# GPS_radiologger_v15.net
KiCad netlist of a schematic drawn in EAGLE
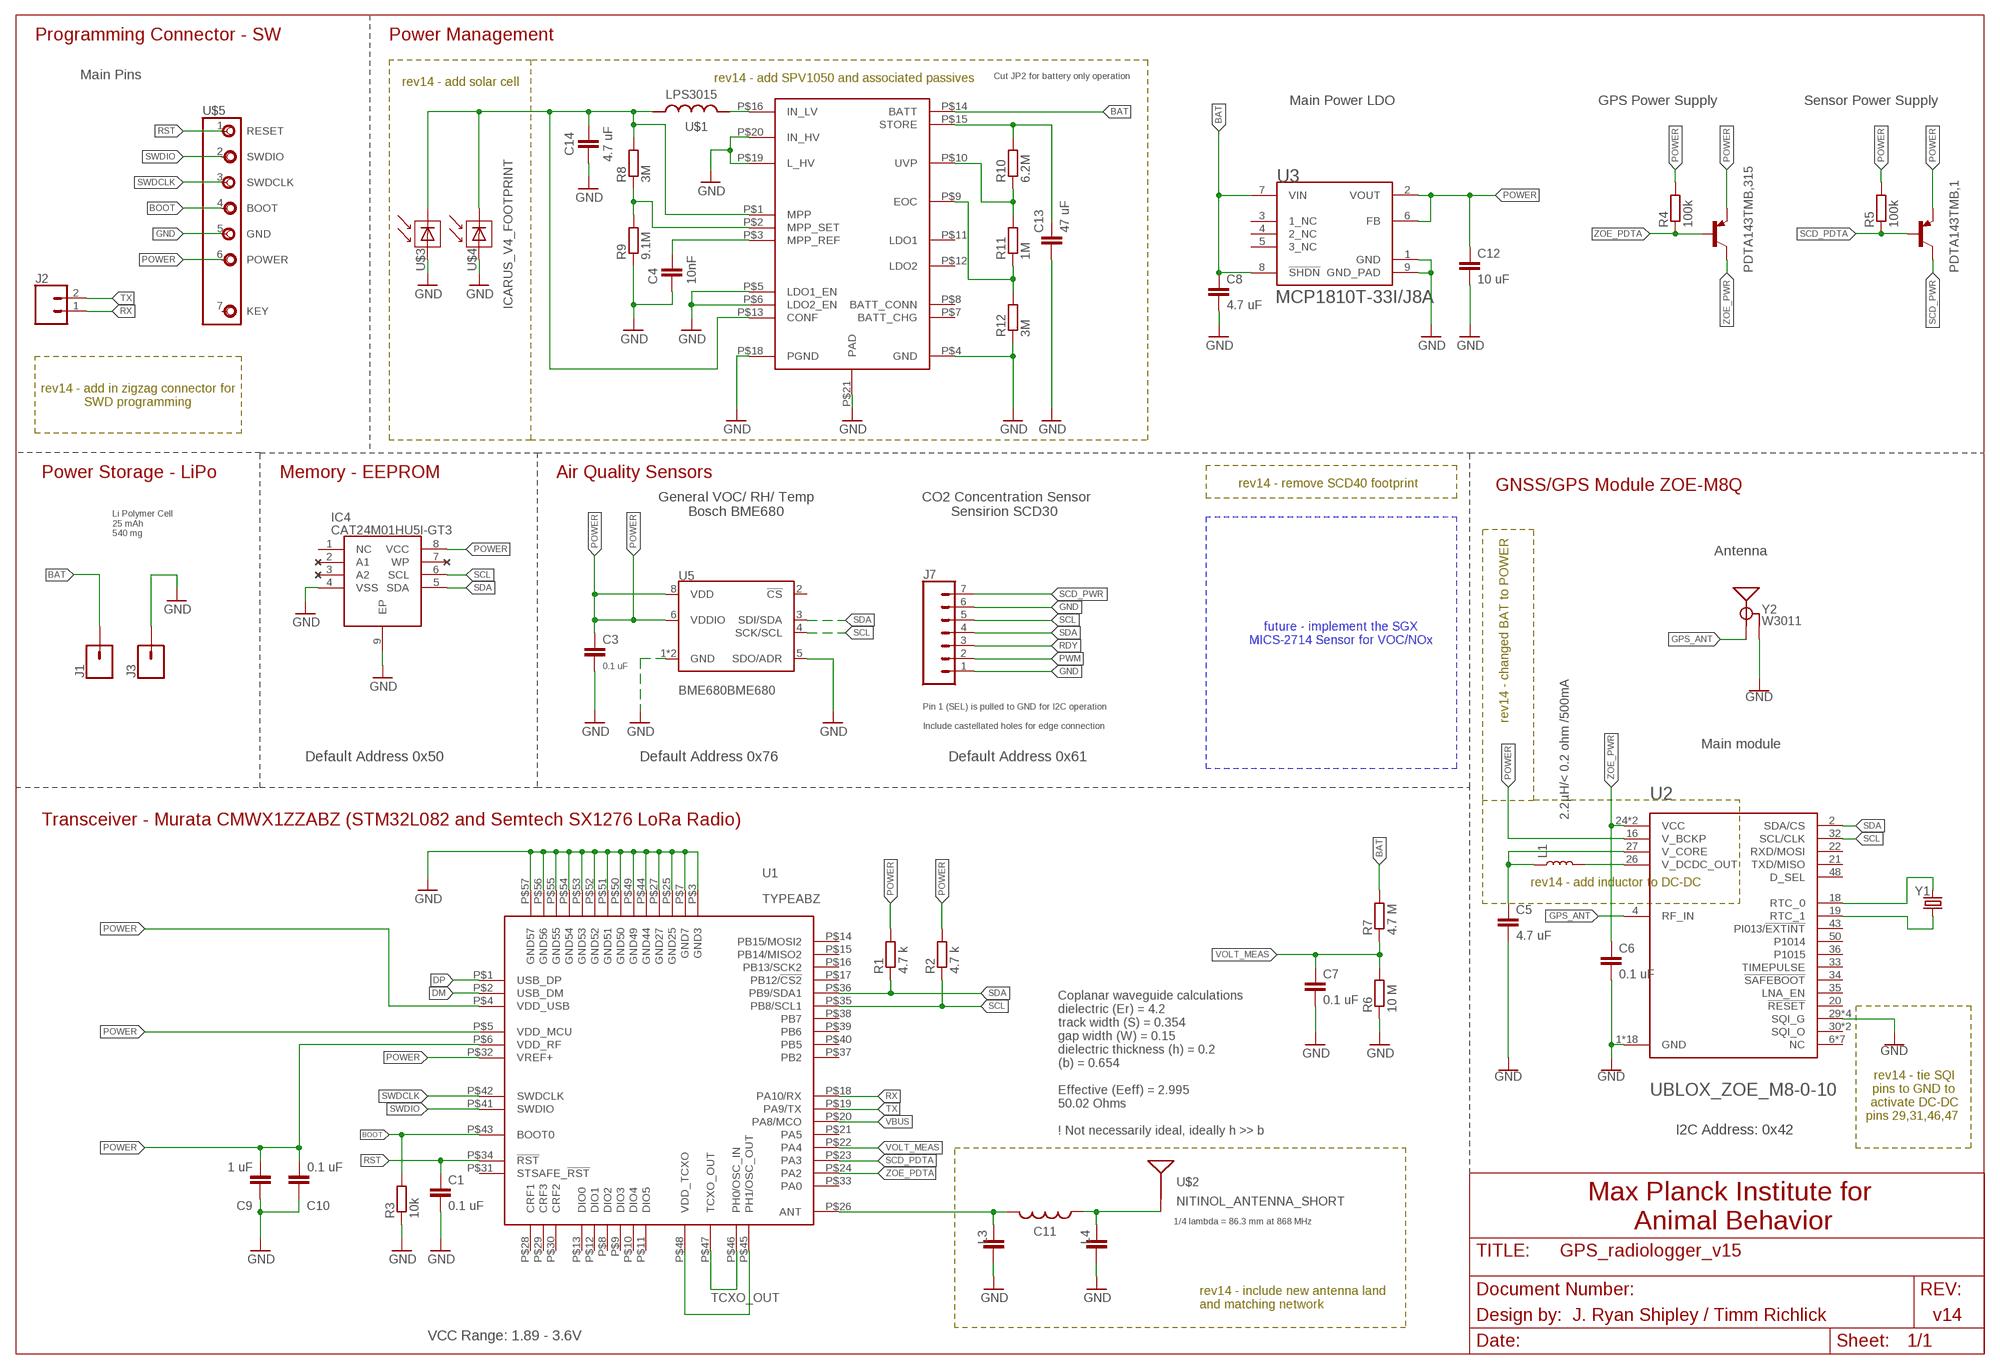
[diagram p0: schematic, sheet 1]

(export (version "E")
  (design (tool "Eeschema 10.0.6"))
  (components
    (comp (ref "C1")
      (value "0.1 uF")
      (footprint "eagle-import:C0201")
      (libsource (lib "eagle-import") (part "C-EUC0201"))
    )
    (comp (ref "C3")
      (value "0.1 uF")
      (footprint "eagle-import:C0201")
      (libsource (lib "eagle-import") (part "C-EUC0201"))
    )
    (comp (ref "C4")
      (value "10nF")
      (footprint "eagle-import:C0201")
      (libsource (lib "eagle-import") (part "C-EUC0201"))
    )
    (comp (ref "C5")
      (value "4.7 uF")
      (footprint "eagle-import:C0201")
      (libsource (lib "eagle-import") (part "C-EUC0201"))
    )
    (comp (ref "C6")
      (value "0.1 uF")
      (footprint "eagle-import:C0201")
      (libsource (lib "eagle-import") (part "C-EUC0201"))
    )
    (comp (ref "C7")
      (value "0.1 uF")
      (footprint "eagle-import:C0201")
      (libsource (lib "eagle-import") (part "C-EUC0201"))
    )
    (comp (ref "C8")
      (value "4.7 uF")
      (footprint "eagle-import:C0201")
      (libsource (lib "eagle-import") (part "C-EUC0201"))
    )
    (comp (ref "C9")
      (value "1 uF")
      (footprint "eagle-import:C0201")
      (libsource (lib "eagle-import") (part "C-EUC0201"))
    )
    (comp (ref "C10")
      (value "0.1 uF")
      (footprint "eagle-import:C0201")
      (libsource (lib "eagle-import") (part "C-EUC0201"))
    )
    (comp (ref "C11")
      (value "0.1uF")
      (footprint "eagle-import:L0201")
      (libsource (lib "eagle-import") (part "L-USL0201"))
    )
    (comp (ref "C12")
      (value "10 uF")
      (footprint "eagle-import:C0201")
      (libsource (lib "eagle-import") (part "C-EUC0201"))
    )
    (comp (ref "C13")
      (value "47 uF")
      (footprint "eagle-import:C0805K")
      (libsource (lib "eagle-import") (part "C-EUC0805K"))
    )
    (comp (ref "C14")
      (value "4.7 uF")
      (footprint "eagle-import:C0201")
      (libsource (lib "eagle-import") (part "C-EUC0201"))
    )
    (comp (ref "IC4")
      (value "CAT24M01HU5I-GT3")
      (footprint "eagle-import:SON50P300X200X55-9N")
      (fields
        (field (name "MOUSER_PART_NUMBER") "863-CAT24M01HU5I-GT3")
        (field (name "RS_PART_NUMBER") "7814831P")
      )
      (libsource (lib "eagle-import") (part "CAT24M01HU5I-GT3"))
    )
    (comp (ref "J1")
      (value "CONN_01PTH_NO_SILK_YES_STOP")
      (footprint "eagle-import:1X01_NO_SILK")
      (libsource (lib "eagle-import") (part "CONN_01PTH_NO_SILK_YES_STOP"))
    )
    (comp (ref "J2")
      (value "CONN_021X02_NO_SILK")
      (footprint "eagle-import:1X02_NO_SILK")
      (libsource (lib "eagle-import") (part "CONN_021X02_NO_SILK"))
    )
    (comp (ref "J3")
      (value "CONN_01PTH_NO_SILK_YES_STOP")
      (footprint "eagle-import:1X01_NO_SILK")
      (libsource (lib "eagle-import") (part "CONN_01PTH_NO_SILK_YES_STOP"))
    )
    (comp (ref "J7")
      (value "CONN_07NO_SILK")
      (footprint "eagle-import:1X07_NO_SILK")
      (libsource (lib "eagle-import") (part "CONN_07NO_SILK"))
    )
    (comp (ref "L1")
      (value "2.2µH/< 0.2 ohm /500mA")
      (footprint "eagle-import:0805")
      (libsource (lib "eagle-import") (part "INDUCTOR-0805-3.3UH"))
    )
    (comp (ref "L3")
      (value "C-EUC0201")
      (footprint "eagle-import:C0201")
      (libsource (lib "eagle-import") (part "C-EUC0201"))
    )
    (comp (ref "L4")
      (value "C-EUC0201")
      (footprint "eagle-import:C0201")
      (libsource (lib "eagle-import") (part "C-EUC0201"))
    )
    (comp (ref "PDTA143TMB,1")
      (value "TINYPICO-PNPAMB")
      (footprint "eagle-import:SOT883(B)")
      (libsource (lib "eagle-import") (part "TINYPICO-PNPMBA"))
    )
    (comp (ref "PDTA143TMB,315")
      (value "TINYPICO-PNPAMB")
      (footprint "eagle-import:SOT883(B)")
      (libsource (lib "eagle-import") (part "TINYPICO-PNPMBA"))
    )
    (comp (ref "R1")
      (value "4.7 k")
      (footprint "eagle-import:R0201")
      (libsource (lib "eagle-import") (part "R-EU_R0201"))
    )
    (comp (ref "R2")
      (value "4.7 k")
      (footprint "eagle-import:R0201")
      (libsource (lib "eagle-import") (part "R-EU_R0201"))
    )
    (comp (ref "R3")
      (value "10k")
      (footprint "eagle-import:R0201")
      (libsource (lib "eagle-import") (part "R-EU_R0201"))
    )
    (comp (ref "R4")
      (value "100k")
      (footprint "eagle-import:R0201")
      (libsource (lib "eagle-import") (part "R-EU_R0201"))
    )
    (comp (ref "R5")
      (value "100k")
      (footprint "eagle-import:R0201")
      (libsource (lib "eagle-import") (part "R-EU_R0201"))
    )
    (comp (ref "R6")
      (value "10 M")
      (footprint "eagle-import:R0201")
      (libsource (lib "eagle-import") (part "R-EU_R0201"))
    )
    (comp (ref "R7")
      (value "4.7 M")
      (footprint "eagle-import:R0201")
      (libsource (lib "eagle-import") (part "R-EU_R0201"))
    )
    (comp (ref "R8")
      (value "3M")
      (footprint "eagle-import:R0201")
      (libsource (lib "eagle-import") (part "R-EU_R0201"))
    )
    (comp (ref "R9")
      (value "9.1M")
      (footprint "eagle-import:R0201")
      (libsource (lib "eagle-import") (part "R-EU_R0201"))
    )
    (comp (ref "R10")
      (value "6.2M")
      (footprint "eagle-import:R0201")
      (libsource (lib "eagle-import") (part "R-EU_R0201"))
    )
    (comp (ref "R11")
      (value "1M")
      (footprint "eagle-import:R0201")
      (libsource (lib "eagle-import") (part "R-EU_R0201"))
    )
    (comp (ref "R12")
      (value "3M")
      (footprint "eagle-import:R0201")
      (libsource (lib "eagle-import") (part "R-EU_R0201"))
    )
    (comp (ref "U$1")
      (value "LPS3015")
      (footprint "eagle-import:LPS_3015")
      (libsource (lib "eagle-import") (part "LPS3015"))
    )
    (comp (ref "U$2")
      (value "NITINOL_ANTENNA_SHORT")
      (footprint "eagle-import:ICARUS_NITINOL_ANTENNA_SHORT")
      (libsource (lib "eagle-import") (part "NITINOL_ANTENNA_SHORT"))
    )
    (comp (ref "U$3")
      (value "ICARUS_V4_FOOTPRINT")
      (footprint "eagle-import:ICARUS_FULL_FOOTPRINT")
      (libsource (lib "eagle-import") (part "ICARUS_V4_FOOTPRINT"))
    )
    (comp (ref "U$4")
      (value "ICARUS_V4_FOOTPRINT")
      (footprint "eagle-import:ICARUS_FULL_FOOTPRINT")
      (libsource (lib "eagle-import") (part "ICARUS_V4_FOOTPRINT"))
    )
    (comp (ref "U$5")
      (value "ALBERT_ZIGZAG-ISP")
      (footprint "eagle-import:ALBERT_ZIGZAG-ISP")
      (libsource (lib "eagle-import") (part "ALBERT_ZIGZAG-ISP"))
    )
    (comp (ref "U1")
      (value "TYPEABZ")
      (footprint "eagle-import:TYPEABZ")
      (libsource (lib "eagle-import") (part "TYPEABZ"))
    )
    (comp (ref "U2")
      (value "UBLOX_ZOE_M8-0-10")
      (footprint "eagle-import:UBLOX_ZOE_M8-0-10")
      (libsource (lib "eagle-import") (part "UBLOX_ZOE_M8-0-10"))
    )
    (comp (ref "U3")
      (value "MICROCHIP_MCP1810T-33I-J8AMICROCHIP_MCP1810T-33I-J8A_0_0")
      (footprint "eagle-import:MICROCHIP_MCP1810T-33I-J8A_0")
      (fields
        (field (name "DIGIKEY_PART_NUMBER") "MCP1810T-33I/J8ACT-ND")
        (field (name "MF") "Microchip")
        (field (name "MOUSER_PART_NUMBER") "579-MCP1810T-33I/J8A")
      )
      (libsource (lib "eagle-import") (part "MICROCHIP_MCP1810T-33I-J8AMICROCHIP_MCP1810T-33I-J8A_0_0"))
    )
    (comp (ref "U4")
      (value "SPV1050")
      (footprint "eagle-import:SPV1050")
      (libsource (lib "eagle-import") (part "SPV1050"))
    )
    (comp (ref "U5")
      (value "BME680BME680")
      (footprint "eagle-import:LGA3.0X3.0")
      (libsource (lib "eagle-import") (part "BME680BME680"))
    )
    (comp (ref "Y1")
      (value "32.768kHz")
      (footprint "eagle-import:CRYSTAL-SMD-1.0X1.2MM")
      (libsource (lib "eagle-import") (part "CRYSTAL-32.768KHZ"))
    )
    (comp (ref "Y2")
      (value "W3011")
      (footprint "eagle-import:W3011")
      (libsource (lib "eagle-import") (part "GPS_CHIP_ANTENNAW3011"))
    )
  )
  (nets
    (net (code "1") (name "/TCXO_OUT") (class "Default")
      (node (ref "U1") (pin "P$46") (pinfunction "PH0/OSC_IN_P$46") (pintype "bidirectional"))
      (node (ref "U1") (pin "P$47") (pinfunction "TCXO_OUT_P$47") (pintype "bidirectional"))
    )
    (net (code "2") (name "BAT") (class "Default")
      (node (ref "C8") (pin "1") (pinfunction "1_1") (pintype "passive"))
      (node (ref "J1") (pin "1") (pinfunction "1_1") (pintype "passive"))
      (node (ref "R7") (pin "2") (pinfunction "2_2") (pintype "passive"))
      (node (ref "U3") (pin "7") (pinfunction "VIN_7") (pintype "bidirectional"))
      (node (ref "U3") (pin "8") (pinfunction "~{SHDN}_8") (pintype "bidirectional"))
      (node (ref "U4") (pin "P$14") (pinfunction "BATT_P$14") (pintype "bidirectional"))
    )
    (net (code "3") (name "BOOT") (class "Default")
      (node (ref "R3") (pin "2") (pinfunction "2_2") (pintype "passive"))
      (node (ref "U$5") (pin "4") (pinfunction "BOOT_4") (pintype "passive"))
      (node (ref "U1") (pin "P$43") (pinfunction "BOOT0_P$43") (pintype "bidirectional"))
    )
    (net (code "4") (name "DM") (class "Default")
      (node (ref "U1") (pin "P$2") (pinfunction "USB_DM_P$2") (pintype "bidirectional"))
    )
    (net (code "5") (name "DP") (class "Default")
      (node (ref "U1") (pin "P$1") (pinfunction "USB_DP_P$1") (pintype "bidirectional"))
    )
    (net (code "6") (name "GND") (class "Default")
      (node (ref "C1") (pin "2") (pinfunction "2_2") (pintype "passive"))
      (node (ref "C10") (pin "1") (pinfunction "1_1") (pintype "passive"))
      (node (ref "C12") (pin "2") (pinfunction "2_2") (pintype "passive"))
      (node (ref "C13") (pin "2") (pinfunction "2_2") (pintype "passive"))
      (node (ref "C14") (pin "2") (pinfunction "2_2") (pintype "passive"))
      (node (ref "C3") (pin "2") (pinfunction "2_2") (pintype "passive"))
      (node (ref "C4") (pin "2") (pinfunction "2_2") (pintype "passive"))
      (node (ref "C5") (pin "2") (pinfunction "2_2") (pintype "passive"))
      (node (ref "C6") (pin "2") (pinfunction "2_2") (pintype "passive"))
      (node (ref "C7") (pin "2") (pinfunction "2_2") (pintype "passive"))
      (node (ref "C8") (pin "2") (pinfunction "2_2") (pintype "passive"))
      (node (ref "C9") (pin "1") (pinfunction "1_1") (pintype "passive"))
      (node (ref "IC4") (pin "4") (pinfunction "VSS_4") (pintype "power_in"))
      (node (ref "IC4") (pin "9") (pinfunction "EP_9") (pintype "bidirectional"))
      (node (ref "J3") (pin "1") (pinfunction "1_1") (pintype "passive"))
      (node (ref "J7") (pin "1") (pinfunction "1_1") (pintype "passive"))
      (node (ref "J7") (pin "6") (pinfunction "6_6") (pintype "passive"))
      (node (ref "L3") (pin "2") (pinfunction "2_2") (pintype "passive"))
      (node (ref "L4") (pin "2") (pinfunction "2_2") (pintype "passive"))
      (node (ref "R12") (pin "1") (pinfunction "1_1") (pintype "passive"))
      (node (ref "R3") (pin "1") (pinfunction "1_1") (pintype "passive"))
      (node (ref "R6") (pin "1") (pinfunction "1_1") (pintype "passive"))
      (node (ref "R9") (pin "1") (pinfunction "1_1") (pintype "passive"))
      (node (ref "U$3") (pin "P$3") (pinfunction "MINUS_P$3") (pintype "passive"))
      (node (ref "U$4") (pin "P$3") (pinfunction "MINUS_P$3") (pintype "passive"))
      (node (ref "U$5") (pin "5") (pinfunction "GND_5") (pintype "passive"))
      (node (ref "U1") (pin "P$25") (pinfunction "GND25_P$25") (pintype "power_in"))
      (node (ref "U1") (pin "P$27") (pinfunction "GND27_P$27") (pintype "power_in"))
      (node (ref "U1") (pin "P$3") (pinfunction "GND3_P$3") (pintype "power_in"))
      (node (ref "U1") (pin "P$44") (pinfunction "GND44_P$44") (pintype "power_in"))
      (node (ref "U1") (pin "P$49") (pinfunction "GND49_P$49") (pintype "power_in"))
      (node (ref "U1") (pin "P$50") (pinfunction "GND50_P$50") (pintype "power_in"))
      (node (ref "U1") (pin "P$51") (pinfunction "GND51_P$51") (pintype "power_in"))
      (node (ref "U1") (pin "P$52") (pinfunction "GND52_P$52") (pintype "power_in"))
      (node (ref "U1") (pin "P$53") (pinfunction "GND53_P$53") (pintype "power_in"))
      (node (ref "U1") (pin "P$54") (pinfunction "GND54_P$54") (pintype "power_in"))
      (node (ref "U1") (pin "P$55") (pinfunction "GND55_P$55") (pintype "power_in"))
      (node (ref "U1") (pin "P$56") (pinfunction "GND56_P$56") (pintype "power_in"))
      (node (ref "U1") (pin "P$57") (pinfunction "GND57_P$57") (pintype "power_in"))
      (node (ref "U1") (pin "P$7") (pinfunction "GND7_P$7") (pintype "power_in"))
      (node (ref "U2") (pin "1") (pinfunction "GND_1") (pintype "power_in"))
      (node (ref "U2") (pin "10") (pinfunction "GND_10") (pintype "power_in"))
      (node (ref "U2") (pin "11") (pinfunction "GND_11") (pintype "power_in"))
      (node (ref "U2") (pin "12") (pinfunction "GND_12") (pintype "power_in"))
      (node (ref "U2") (pin "17") (pinfunction "GND_17") (pintype "power_in"))
      (node (ref "U2") (pin "23") (pinfunction "GND_23") (pintype "power_in"))
      (node (ref "U2") (pin "29") (pinfunction "SQI_G_29") (pintype "bidirectional"))
      (node (ref "U2") (pin "3") (pinfunction "GND_3") (pintype "power_in"))
      (node (ref "U2") (pin "31") (pinfunction "SQI_G_31") (pintype "bidirectional"))
      (node (ref "U2") (pin "37") (pinfunction "GND_37") (pintype "power_in"))
      (node (ref "U2") (pin "38") (pinfunction "GND_38") (pintype "power_in"))
      (node (ref "U2") (pin "39") (pinfunction "GND_39") (pintype "power_in"))
      (node (ref "U2") (pin "40") (pinfunction "GND_40") (pintype "power_in"))
      (node (ref "U2") (pin "41") (pinfunction "GND_41") (pintype "power_in"))
      (node (ref "U2") (pin "44") (pinfunction "GND_44") (pintype "power_in"))
      (node (ref "U2") (pin "46") (pinfunction "SQI_G_46") (pintype "bidirectional"))
      (node (ref "U2") (pin "47") (pinfunction "SQI_G_47") (pintype "bidirectional"))
      (node (ref "U2") (pin "49") (pinfunction "GND_49") (pintype "power_in"))
      (node (ref "U2") (pin "5") (pinfunction "GND_5") (pintype "power_in"))
      (node (ref "U2") (pin "7") (pinfunction "GND_7") (pintype "power_in"))
      (node (ref "U2") (pin "8") (pinfunction "GND_8") (pintype "power_in"))
      (node (ref "U2") (pin "9") (pinfunction "GND_9") (pintype "power_in"))
      (node (ref "U3") (pin "1") (pinfunction "GND_1") (pintype "bidirectional"))
      (node (ref "U3") (pin "9") (pinfunction "GND_PAD_9") (pintype "bidirectional"))
      (node (ref "U4") (pin "P$18") (pinfunction "PGND_P$18") (pintype "power_in"))
      (node (ref "U4") (pin "P$19") (pinfunction "L_HV_P$19") (pintype "power_in"))
      (node (ref "U4") (pin "P$20") (pinfunction "IN_HV_P$20") (pintype "power_in"))
      (node (ref "U4") (pin "P$21") (pinfunction "PAD_P$21") (pintype "power_in"))
      (node (ref "U4") (pin "P$4") (pinfunction "GND_P$4") (pintype "power_in"))
      (node (ref "U4") (pin "P$5") (pinfunction "LDO1_EN_P$5") (pintype "input"))
      (node (ref "U4") (pin "P$6") (pinfunction "LDO2_EN_P$6") (pintype "input"))
      (node (ref "U5") (pin "1") (pinfunction "GND_1") (pintype "bidirectional"))
      (node (ref "U5") (pin "5") (pinfunction "SDO/ADR_5") (pintype "bidirectional"))
      (node (ref "U5") (pin "7") (pinfunction "GND_7") (pintype "bidirectional"))
      (node (ref "Y2") (pin "2") (pinfunction "GND_2") (pintype "bidirectional"))
      (node (ref "Y2") (pin "3") (pinfunction "GND_3") (pintype "bidirectional"))
    )
    (net (code "7") (name "GPS_ANT") (class "Default")
      (node (ref "U2") (pin "4") (pinfunction "RF_IN_4") (pintype "bidirectional"))
      (node (ref "Y2") (pin "1") (pinfunction "SIGNAL_1") (pintype "bidirectional"))
    )
    (net (code "8") (name "Net-(C11-Pad1)") (class "Default")
      (node (ref "C11") (pin "1") (pinfunction "1_1") (pintype "passive"))
      (node (ref "L4") (pin "1") (pinfunction "1_1") (pintype "passive"))
      (node (ref "U$2") (pin "1") (pinfunction "SIGNAL_1") (pintype "bidirectional"))
      (node (ref "U$2") (pin "2") (pinfunction "SIGNAL_2") (pintype "bidirectional"))
      (node (ref "U$2") (pin "3") (pinfunction "SIGNAL_3") (pintype "bidirectional"))
    )
    (net (code "9") (name "Net-(U$1-1)") (class "Default")
      (node (ref "C14") (pin "1") (pinfunction "1_1") (pintype "passive"))
      (node (ref "R8") (pin "2") (pinfunction "2_2") (pintype "passive"))
      (node (ref "U$1") (pin "P$1") (pinfunction "1_P$1") (pintype "passive"))
      (node (ref "U$3") (pin "P$1") (pinfunction "PLUS_P$1") (pintype "passive"))
      (node (ref "U$4") (pin "P$1") (pinfunction "PLUS_P$1") (pintype "passive"))
      (node (ref "U4") (pin "P$1") (pinfunction "MPP_P$1") (pintype "input"))
      (node (ref "U4") (pin "P$13") (pinfunction "CONF_P$13") (pintype "input"))
    )
    (net (code "10") (name "Net-(U$1-2)") (class "Default")
      (node (ref "U$1") (pin "P$2") (pinfunction "2_P$2") (pintype "passive"))
      (node (ref "U4") (pin "P$16") (pinfunction "IN_LV_P$16") (pintype "power_in"))
    )
    (net (code "11") (name "Net-(U1-ANT)") (class "Default")
      (node (ref "C11") (pin "2") (pinfunction "2_2") (pintype "passive"))
      (node (ref "L3") (pin "1") (pinfunction "1_1") (pintype "passive"))
      (node (ref "U1") (pin "P$26") (pinfunction "ANT_P$26") (pintype "bidirectional"))
    )
    (net (code "12") (name "Net-(U1-PH1{slash}OSC_OUT)") (class "Default")
      (node (ref "U1") (pin "P$45") (pinfunction "PH1/OSC_OUT_P$45") (pintype "bidirectional"))
      (node (ref "U1") (pin "P$48") (pinfunction "VDD_TCXO_P$48") (pintype "power_in"))
    )
    (net (code "13") (name "Net-(U2-RTC_0)") (class "Default")
      (node (ref "U2") (pin "18") (pinfunction "RTC_0_18") (pintype "bidirectional"))
      (node (ref "Y1") (pin "P$2") (pinfunction "2_P$2") (pintype "passive"))
    )
    (net (code "14") (name "Net-(U2-RTC_1)") (class "Default")
      (node (ref "U2") (pin "19") (pinfunction "RTC_1_19") (pintype "bidirectional"))
      (node (ref "Y1") (pin "P$1") (pinfunction "1_P$1") (pintype "passive"))
    )
    (net (code "15") (name "Net-(U2-V_CORE)") (class "Default")
      (node (ref "C5") (pin "1") (pinfunction "1_1") (pintype "passive"))
      (node (ref "L1") (pin "1") (pinfunction "1_1") (pintype "passive"))
      (node (ref "U2") (pin "27") (pinfunction "V_CORE_27") (pintype "power_in"))
    )
    (net (code "16") (name "Net-(U2-V_DCDC_OUT)") (class "Default")
      (node (ref "L1") (pin "2") (pinfunction "2_2") (pintype "passive"))
      (node (ref "U2") (pin "26") (pinfunction "V_DCDC_OUT_26") (pintype "power_in"))
    )
    (net (code "17") (name "Net-(U4-EOC)") (class "Default")
      (node (ref "R11") (pin "1") (pinfunction "1_1") (pintype "passive"))
      (node (ref "R12") (pin "2") (pinfunction "2_2") (pintype "passive"))
      (node (ref "U4") (pin "P$9") (pinfunction "EOC_P$9") (pintype "input"))
    )
    (net (code "18") (name "Net-(U4-MPP_REF)") (class "Default")
      (node (ref "C4") (pin "1") (pinfunction "1_1") (pintype "passive"))
      (node (ref "U4") (pin "P$3") (pinfunction "MPP_REF_P$3") (pintype "input"))
    )
    (net (code "19") (name "Net-(U4-MPP_SET)") (class "Default")
      (node (ref "R8") (pin "1") (pinfunction "1_1") (pintype "passive"))
      (node (ref "R9") (pin "2") (pinfunction "2_2") (pintype "passive"))
      (node (ref "U4") (pin "P$2") (pinfunction "MPP_SET_P$2") (pintype "input"))
    )
    (net (code "20") (name "Net-(U4-STORE)") (class "Default")
      (node (ref "C13") (pin "1") (pinfunction "1_1") (pintype "passive"))
      (node (ref "R10") (pin "2") (pinfunction "2_2") (pintype "passive"))
      (node (ref "U4") (pin "P$15") (pinfunction "STORE_P$15") (pintype "bidirectional"))
    )
    (net (code "21") (name "Net-(U4-UVP)") (class "Default")
      (node (ref "R10") (pin "1") (pinfunction "1_1") (pintype "passive"))
      (node (ref "R11") (pin "2") (pinfunction "2_2") (pintype "passive"))
      (node (ref "U4") (pin "P$10") (pinfunction "UVP_P$10") (pintype "input"))
    )
    (net (code "22") (name "POWER") (class "Default")
      (node (ref "C10") (pin "2") (pinfunction "2_2") (pintype "passive"))
      (node (ref "C12") (pin "1") (pinfunction "1_1") (pintype "passive"))
      (node (ref "C3") (pin "1") (pinfunction "1_1") (pintype "passive"))
      (node (ref "C9") (pin "2") (pinfunction "2_2") (pintype "passive"))
      (node (ref "IC4") (pin "8") (pinfunction "VCC_8") (pintype "power_in"))
      (node (ref "PDTA143TMB,1") (pin "2") (pinfunction "E_2") (pintype "passive"))
      (node (ref "PDTA143TMB,315") (pin "2") (pinfunction "E_2") (pintype "passive"))
      (node (ref "R1") (pin "2") (pinfunction "2_2") (pintype "passive"))
      (node (ref "R2") (pin "2") (pinfunction "2_2") (pintype "passive"))
      (node (ref "R4") (pin "2") (pinfunction "2_2") (pintype "passive"))
      (node (ref "R5") (pin "2") (pinfunction "2_2") (pintype "passive"))
      (node (ref "U$5") (pin "6") (pinfunction "POWER_6") (pintype "passive"))
      (node (ref "U1") (pin "P$32") (pinfunction "VREF+_P$32") (pintype "power_in"))
      (node (ref "U1") (pin "P$4") (pinfunction "VDD_USB_P$4") (pintype "power_in"))
      (node (ref "U1") (pin "P$5") (pinfunction "VDD_MCU_P$5") (pintype "power_in"))
      (node (ref "U1") (pin "P$6") (pinfunction "VDD_RF_P$6") (pintype "power_in"))
      (node (ref "U2") (pin "16") (pinfunction "V_BCKP_16") (pintype "power_in"))
      (node (ref "U3") (pin "2") (pinfunction "VOUT_2") (pintype "bidirectional"))
      (node (ref "U3") (pin "6") (pinfunction "FB_6") (pintype "bidirectional"))
      (node (ref "U5") (pin "6") (pinfunction "VDDIO_6") (pintype "bidirectional"))
      (node (ref "U5") (pin "8") (pinfunction "VDD_8") (pintype "bidirectional"))
    )
    (net (code "23") (name "PWM") (class "Default")
      (node (ref "J7") (pin "2") (pinfunction "2_2") (pintype "passive"))
    )
    (net (code "24") (name "RDY") (class "Default")
      (node (ref "J7") (pin "3") (pinfunction "3_3") (pintype "passive"))
    )
    (net (code "25") (name "RST") (class "Default")
      (node (ref "C1") (pin "1") (pinfunction "1_1") (pintype "passive"))
      (node (ref "U$5") (pin "1") (pinfunction "RESET_1") (pintype "passive"))
      (node (ref "U1") (pin "P$34") (pinfunction "~{RST}_P$34") (pintype "bidirectional"))
    )
    (net (code "26") (name "RX") (class "Default")
      (node (ref "J2") (pin "1") (pinfunction "1_1") (pintype "passive"))
      (node (ref "U1") (pin "P$18") (pinfunction "PA10/RX_P$18") (pintype "bidirectional"))
    )
    (net (code "27") (name "SCD_PDTA") (class "Default")
      (node (ref "PDTA143TMB,1") (pin "1") (pinfunction "B_1") (pintype "passive"))
      (node (ref "R5") (pin "1") (pinfunction "1_1") (pintype "passive"))
      (node (ref "U1") (pin "P$23") (pinfunction "PA3_P$23") (pintype "bidirectional"))
    )
    (net (code "28") (name "SCD_PWR") (class "Default")
      (node (ref "J7") (pin "7") (pinfunction "7_7") (pintype "passive"))
      (node (ref "PDTA143TMB,1") (pin "3") (pinfunction "C_3") (pintype "passive"))
    )
    (net (code "29") (name "SCL") (class "Default")
      (node (ref "IC4") (pin "6") (pinfunction "SCL_6") (pintype "bidirectional"))
      (node (ref "J7") (pin "5") (pinfunction "5_5") (pintype "passive"))
      (node (ref "R2") (pin "1") (pinfunction "1_1") (pintype "passive"))
      (node (ref "U1") (pin "P$35") (pinfunction "PB8/SCL1_P$35") (pintype "bidirectional"))
      (node (ref "U2") (pin "32") (pinfunction "SCL/CLK_32") (pintype "bidirectional"))
      (node (ref "U5") (pin "4") (pinfunction "SCK/SCL_4") (pintype "bidirectional"))
    )
    (net (code "30") (name "SDA") (class "Default")
      (node (ref "IC4") (pin "5") (pinfunction "SDA_5") (pintype "bidirectional"))
      (node (ref "J7") (pin "4") (pinfunction "4_4") (pintype "passive"))
      (node (ref "R1") (pin "1") (pinfunction "1_1") (pintype "passive"))
      (node (ref "U1") (pin "P$36") (pinfunction "PB9/SDA1_P$36") (pintype "bidirectional"))
      (node (ref "U2") (pin "2") (pinfunction "SDA/CS_2") (pintype "bidirectional"))
      (node (ref "U5") (pin "3") (pinfunction "SDI/SDA_3") (pintype "bidirectional"))
    )
    (net (code "31") (name "SWDCLK") (class "Default")
      (node (ref "U$5") (pin "3") (pinfunction "SWDCLK_3") (pintype "passive"))
      (node (ref "U1") (pin "P$42") (pinfunction "SWDCLK_P$42") (pintype "bidirectional"))
    )
    (net (code "32") (name "SWDIO") (class "Default")
      (node (ref "U$5") (pin "2") (pinfunction "SWDIO_2") (pintype "passive"))
      (node (ref "U1") (pin "P$41") (pinfunction "SWDIO_P$41") (pintype "bidirectional"))
    )
    (net (code "33") (name "TX") (class "Default")
      (node (ref "J2") (pin "2") (pinfunction "2_2") (pintype "passive"))
      (node (ref "U1") (pin "P$19") (pinfunction "PA9/TX_P$19") (pintype "bidirectional"))
    )
    (net (code "34") (name "VBUS") (class "Default")
      (node (ref "U1") (pin "P$20") (pinfunction "PA8/MCO_P$20") (pintype "bidirectional"))
    )
    (net (code "35") (name "VOLT_MEAS") (class "Default")
      (node (ref "C7") (pin "1") (pinfunction "1_1") (pintype "passive"))
      (node (ref "R6") (pin "2") (pinfunction "2_2") (pintype "passive"))
      (node (ref "R7") (pin "1") (pinfunction "1_1") (pintype "passive"))
      (node (ref "U1") (pin "P$22") (pinfunction "PA4_P$22") (pintype "bidirectional"))
    )
    (net (code "36") (name "ZOE_PDTA") (class "Default")
      (node (ref "PDTA143TMB,315") (pin "1") (pinfunction "B_1") (pintype "passive"))
      (node (ref "R4") (pin "1") (pinfunction "1_1") (pintype "passive"))
      (node (ref "U1") (pin "P$24") (pinfunction "PA2_P$24") (pintype "bidirectional"))
    )
    (net (code "37") (name "ZOE_PWR") (class "Default")
      (node (ref "C6") (pin "1") (pinfunction "1_1") (pintype "passive"))
      (node (ref "PDTA143TMB,315") (pin "3") (pinfunction "C_3") (pintype "passive"))
      (node (ref "U2") (pin "24") (pinfunction "VCC_24") (pintype "power_in"))
      (node (ref "U2") (pin "25") (pinfunction "VCC_25") (pintype "power_in"))
    )
    (net (code "38") (name "unconnected-(IC4-A1-Pad2)") (class "Default")
      (node (ref "IC4") (pin "2") (pinfunction "A1_2") (pintype "bidirectional"))
    )
    (net (code "39") (name "unconnected-(IC4-A2-Pad3)") (class "Default")
      (node (ref "IC4") (pin "3") (pinfunction "A2_3") (pintype "bidirectional"))
    )
    (net (code "40") (name "unconnected-(IC4-NC-Pad1)") (class "Default")
      (node (ref "IC4") (pin "1") (pinfunction "NC_1") (pintype "no_connect"))
    )
    (net (code "41") (name "unconnected-(IC4-WP-Pad7)") (class "Default")
      (node (ref "IC4") (pin "7") (pinfunction "WP_7") (pintype "bidirectional"))
    )
    (net (code "42") (name "unconnected-(U$5-KEY-Pad7)") (class "Default")
      (node (ref "U$5") (pin "7") (pinfunction "KEY_7") (pintype "passive"))
    )
    (net (code "43") (name "unconnected-(U1-CRF1-PadP$28)") (class "Default")
      (node (ref "U1") (pin "P$28") (pinfunction "CRF1_P$28") (pintype "no_connect"))
    )
    (net (code "44") (name "unconnected-(U1-CRF2-PadP$30)") (class "Default")
      (node (ref "U1") (pin "P$30") (pinfunction "CRF2_P$30") (pintype "no_connect"))
    )
    (net (code "45") (name "unconnected-(U1-CRF3-PadP$29)") (class "Default")
      (node (ref "U1") (pin "P$29") (pinfunction "CRF3_P$29") (pintype "no_connect"))
    )
    (net (code "46") (name "unconnected-(U1-DIO0-PadP$13)") (class "Default")
      (node (ref "U1") (pin "P$13") (pinfunction "DIO0_P$13") (pintype "no_connect"))
    )
    (net (code "47") (name "unconnected-(U1-DIO1-PadP$12)") (class "Default")
      (node (ref "U1") (pin "P$12") (pinfunction "DIO1_P$12") (pintype "no_connect"))
    )
    (net (code "48") (name "unconnected-(U1-DIO2-PadP$8)") (class "Default")
      (node (ref "U1") (pin "P$8") (pinfunction "DIO2_P$8") (pintype "no_connect"))
    )
    (net (code "49") (name "unconnected-(U1-DIO3-PadP$9)") (class "Default")
      (node (ref "U1") (pin "P$9") (pinfunction "DIO3_P$9") (pintype "no_connect"))
    )
    (net (code "50") (name "unconnected-(U1-DIO4-PadP$10)") (class "Default")
      (node (ref "U1") (pin "P$10") (pinfunction "DIO4_P$10") (pintype "bidirectional"))
    )
    (net (code "51") (name "unconnected-(U1-DIO5-PadP$11)") (class "Default")
      (node (ref "U1") (pin "P$11") (pinfunction "DIO5_P$11") (pintype "bidirectional"))
    )
    (net (code "52") (name "unconnected-(U1-PA0-PadP$33)") (class "Default")
      (node (ref "U1") (pin "P$33") (pinfunction "PA0_P$33") (pintype "bidirectional"))
    )
    (net (code "53") (name "unconnected-(U1-PA5-PadP$21)") (class "Default")
      (node (ref "U1") (pin "P$21") (pinfunction "PA5_P$21") (pintype "bidirectional"))
    )
    (net (code "54") (name "unconnected-(U1-PB2-PadP$37)") (class "Default")
      (node (ref "U1") (pin "P$37") (pinfunction "PB2_P$37") (pintype "bidirectional"))
    )
    (net (code "55") (name "unconnected-(U1-PB5-PadP$40)") (class "Default")
      (node (ref "U1") (pin "P$40") (pinfunction "PB5_P$40") (pintype "bidirectional"))
    )
    (net (code "56") (name "unconnected-(U1-PB6-PadP$39)") (class "Default")
      (node (ref "U1") (pin "P$39") (pinfunction "PB6_P$39") (pintype "bidirectional"))
    )
    (net (code "57") (name "unconnected-(U1-PB7-PadP$38)") (class "Default")
      (node (ref "U1") (pin "P$38") (pinfunction "PB7_P$38") (pintype "bidirectional"))
    )
    (net (code "58") (name "unconnected-(U1-PB12{slash}~{CS2}-PadP$17)") (class "Default")
      (node (ref "U1") (pin "P$17") (pinfunction "PB12/~{CS2}_P$17") (pintype "bidirectional"))
    )
    (net (code "59") (name "unconnected-(U1-PB13{slash}SCK2-PadP$16)") (class "Default")
      (node (ref "U1") (pin "P$16") (pinfunction "PB13/SCK2_P$16") (pintype "bidirectional"))
    )
    (net (code "60") (name "unconnected-(U1-PB14{slash}MISO2-PadP$15)") (class "Default")
      (node (ref "U1") (pin "P$15") (pinfunction "PB14/MISO2_P$15") (pintype "bidirectional"))
    )
    (net (code "61") (name "unconnected-(U1-PB15{slash}MOSI2-PadP$14)") (class "Default")
      (node (ref "U1") (pin "P$14") (pinfunction "PB15/MOSI2_P$14") (pintype "bidirectional"))
    )
    (net (code "62") (name "unconnected-(U1-STSAFE_~{RST}-PadP$31)") (class "Default")
      (node (ref "U1") (pin "P$31") (pinfunction "STSAFE_~{RST}_P$31") (pintype "bidirectional"))
    )
    (net (code "63") (name "unconnected-(U2-D_SEL-Pad48)") (class "Default")
      (node (ref "U2") (pin "48") (pinfunction "D_SEL_48") (pintype "bidirectional"))
    )
    (net (code "64") (name "unconnected-(U2-LNA_EN-Pad35)") (class "Default")
      (node (ref "U2") (pin "35") (pinfunction "LNA_EN_35") (pintype "bidirectional"))
    )
    (net (code "65") (name "unconnected-(U2-NC-Pad6)") (class "Default")
      (node (ref "U2") (pin "6") (pinfunction "NC_6") (pintype "no_connect"))
    )
    (net (code "66") (name "unconnected-(U2-NC-Pad13)") (class "Default")
      (node (ref "U2") (pin "13") (pinfunction "NC_13") (pintype "no_connect"))
    )
    (net (code "67") (name "unconnected-(U2-NC-Pad14)") (class "Default")
      (node (ref "U2") (pin "14") (pinfunction "NC_14") (pintype "no_connect"))
    )
    (net (code "68") (name "unconnected-(U2-NC-Pad15)") (class "Default")
      (node (ref "U2") (pin "15") (pinfunction "NC_15") (pintype "no_connect"))
    )
    (net (code "69") (name "unconnected-(U2-NC-Pad28)") (class "Default")
      (node (ref "U2") (pin "28") (pinfunction "NC_28") (pintype "no_connect"))
    )
    (net (code "70") (name "unconnected-(U2-NC-Pad42)") (class "Default")
      (node (ref "U2") (pin "42") (pinfunction "NC_42") (pintype "no_connect"))
    )
    (net (code "71") (name "unconnected-(U2-NC-Pad51)") (class "Default")
      (node (ref "U2") (pin "51") (pinfunction "NC_51") (pintype "no_connect"))
    )
    (net (code "72") (name "unconnected-(U2-P1014-Pad50)") (class "Default")
      (node (ref "U2") (pin "50") (pinfunction "P1014_50") (pintype "bidirectional"))
    )
    (net (code "73") (name "unconnected-(U2-P1015-Pad36)") (class "Default")
      (node (ref "U2") (pin "36") (pinfunction "P1015_36") (pintype "bidirectional"))
    )
    (net (code "74") (name "unconnected-(U2-PI013{slash}~{EXTINT}-Pad43)") (class "Default")
      (node (ref "U2") (pin "43") (pinfunction "PI013/~{EXTINT}_43") (pintype "bidirectional"))
    )
    (net (code "75") (name "unconnected-(U2-RXD{slash}MOSI-Pad22)") (class "Default")
      (node (ref "U2") (pin "22") (pinfunction "RXD/MOSI_22") (pintype "bidirectional"))
    )
    (net (code "76") (name "unconnected-(U2-SQI_O-Pad30)") (class "Default")
      (node (ref "U2") (pin "30") (pinfunction "SQI_O_30") (pintype "no_connect"))
    )
    (net (code "77") (name "unconnected-(U2-SQI_O-Pad45)") (class "Default")
      (node (ref "U2") (pin "45") (pinfunction "SQI_O_45") (pintype "no_connect"))
    )
    (net (code "78") (name "unconnected-(U2-TIMEPULSE-Pad33)") (class "Default")
      (node (ref "U2") (pin "33") (pinfunction "TIMEPULSE_33") (pintype "bidirectional"))
    )
    (net (code "79") (name "unconnected-(U2-TXD{slash}MISO-Pad21)") (class "Default")
      (node (ref "U2") (pin "21") (pinfunction "TXD/MISO_21") (pintype "bidirectional"))
    )
    (net (code "80") (name "unconnected-(U2-~{RESET}-Pad20)") (class "Default")
      (node (ref "U2") (pin "20") (pinfunction "~{RESET}_20") (pintype "bidirectional"))
    )
    (net (code "81") (name "unconnected-(U2-~{SAFEBOOT}-Pad34)") (class "Default")
      (node (ref "U2") (pin "34") (pinfunction "~{SAFEBOOT}_34") (pintype "bidirectional"))
    )
    (net (code "82") (name "unconnected-(U3-1_NC-Pad3)") (class "Default")
      (node (ref "U3") (pin "3") (pinfunction "1_NC_3") (pintype "bidirectional"))
    )
    (net (code "83") (name "unconnected-(U3-2_NC-Pad4)") (class "Default")
      (node (ref "U3") (pin "4") (pinfunction "2_NC_4") (pintype "bidirectional"))
    )
    (net (code "84") (name "unconnected-(U3-3_NC-Pad5)") (class "Default")
      (node (ref "U3") (pin "5") (pinfunction "3_NC_5") (pintype "bidirectional"))
    )
    (net (code "85") (name "unconnected-(U4-BATT_CHG-PadP$7)") (class "Default")
      (node (ref "U4") (pin "P$7") (pinfunction "BATT_CHG_P$7") (pintype "open_collector"))
    )
    (net (code "86") (name "unconnected-(U4-BATT_CONN-PadP$8)") (class "Default")
      (node (ref "U4") (pin "P$8") (pinfunction "BATT_CONN_P$8") (pintype "open_collector"))
    )
    (net (code "87") (name "unconnected-(U4-LDO1-PadP$11)") (class "Default")
      (node (ref "U4") (pin "P$11") (pinfunction "LDO1_P$11") (pintype "output"))
    )
    (net (code "88") (name "unconnected-(U4-LDO2-PadP$12)") (class "Default")
      (node (ref "U4") (pin "P$12") (pinfunction "LDO2_P$12") (pintype "output"))
    )
    (net (code "89") (name "unconnected-(U5-~{CS}-Pad2)") (class "Default")
      (node (ref "U5") (pin "2") (pinfunction "~{CS}_2") (pintype "bidirectional"))
    )
  )
)
